# InputModule.net
KiCad netlist of a schematic drawn in EAGLE
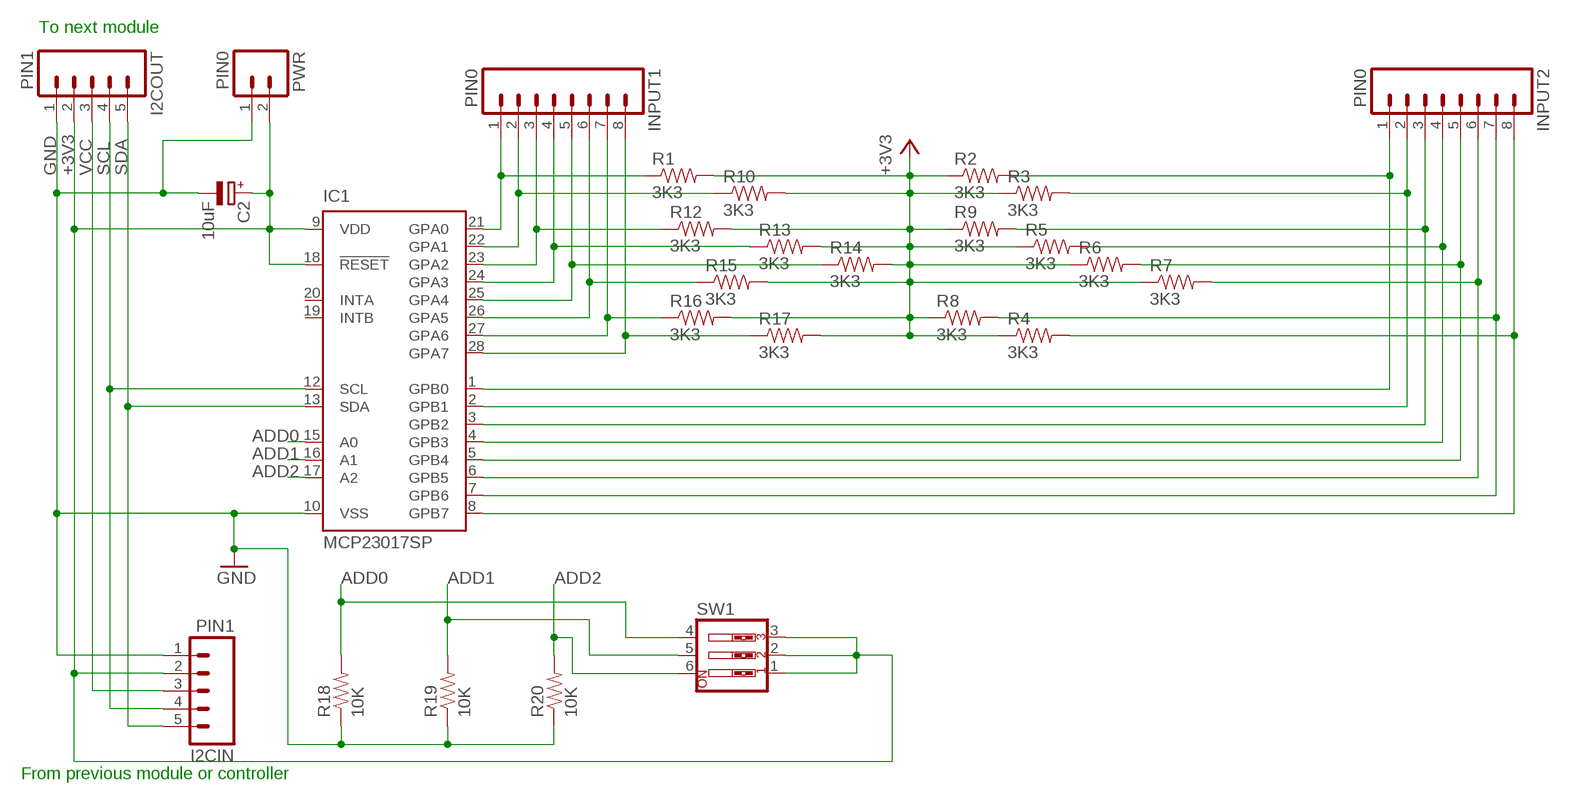
[diagram p0: schematic, sheet 1]

(export (version "E")
  (design (tool "Eeschema 10.0.6"))
  (components
    (comp (ref "C2")
      (value "10uF")
      (footprint "eagle-import:E2,5-6")
      (libsource (lib "eagle-import") (part "CPOL-EUE2.5-6"))
    )
    (comp (ref "I2CIN")
      (value "PIN1")
      (footprint "eagle-import:05P")
      (libsource (lib "eagle-import") (part "M05"))
    )
    (comp (ref "I2COUT")
      (value "PIN1")
      (footprint "eagle-import:05P")
      (libsource (lib "eagle-import") (part "M05"))
    )
    (comp (ref "IC1")
      (value "MCP23017SP")
      (footprint "eagle-import:DIL28-3")
      (fields (field (name "MF") "MICROCHIP") (field (name "MPN") "MCP23017-E/SP"))
      (libsource (lib "eagle-import") (part "MCP23017SP"))
    )
    (comp (ref "INPUT1")
      (value "PIN0")
      (footprint "eagle-import:1X08_ROUND")
      (libsource (lib "eagle-import") (part "M08"))
    )
    (comp (ref "INPUT2")
      (value "PIN0")
      (footprint "eagle-import:1X08_ROUND")
      (libsource (lib "eagle-import") (part "M08"))
    )
    (comp (ref "PWR")
      (value "PIN0")
      (footprint "eagle-import:02P")
      (libsource (lib "eagle-import") (part "M02"))
    )
    (comp (ref "R1")
      (value "3K3")
      (footprint "eagle-import:AXIAL-0.4")
      (libsource (lib "eagle-import") (part "RESISTORPTH-1/4W"))
    )
    (comp (ref "R2")
      (value "3K3")
      (footprint "eagle-import:AXIAL-0.4")
      (libsource (lib "eagle-import") (part "RESISTORPTH-1/4W"))
    )
    (comp (ref "R3")
      (value "3K3")
      (footprint "eagle-import:AXIAL-0.4")
      (libsource (lib "eagle-import") (part "RESISTORPTH-1/4W"))
    )
    (comp (ref "R4")
      (value "3K3")
      (footprint "eagle-import:AXIAL-0.4")
      (libsource (lib "eagle-import") (part "RESISTORPTH-1/4W"))
    )
    (comp (ref "R5")
      (value "3K3")
      (footprint "eagle-import:AXIAL-0.4")
      (libsource (lib "eagle-import") (part "RESISTORPTH-1/4W"))
    )
    (comp (ref "R6")
      (value "3K3")
      (footprint "eagle-import:AXIAL-0.4")
      (libsource (lib "eagle-import") (part "RESISTORPTH-1/4W"))
    )
    (comp (ref "R7")
      (value "3K3")
      (footprint "eagle-import:AXIAL-0.4")
      (libsource (lib "eagle-import") (part "RESISTORPTH-1/4W"))
    )
    (comp (ref "R8")
      (value "3K3")
      (footprint "eagle-import:AXIAL-0.4")
      (libsource (lib "eagle-import") (part "RESISTORPTH-1/4W"))
    )
    (comp (ref "R9")
      (value "3K3")
      (footprint "eagle-import:AXIAL-0.4")
      (libsource (lib "eagle-import") (part "RESISTORPTH-1/4W"))
    )
    (comp (ref "R10")
      (value "3K3")
      (footprint "eagle-import:AXIAL-0.4")
      (libsource (lib "eagle-import") (part "RESISTORPTH-1/4W"))
    )
    (comp (ref "R12")
      (value "3K3")
      (footprint "eagle-import:AXIAL-0.4")
      (libsource (lib "eagle-import") (part "RESISTORPTH-1/4W"))
    )
    (comp (ref "R13")
      (value "3K3")
      (footprint "eagle-import:AXIAL-0.4")
      (libsource (lib "eagle-import") (part "RESISTORPTH-1/4W"))
    )
    (comp (ref "R14")
      (value "3K3")
      (footprint "eagle-import:AXIAL-0.4")
      (libsource (lib "eagle-import") (part "RESISTORPTH-1/4W"))
    )
    (comp (ref "R15")
      (value "3K3")
      (footprint "eagle-import:AXIAL-0.4")
      (libsource (lib "eagle-import") (part "RESISTORPTH-1/4W"))
    )
    (comp (ref "R16")
      (value "3K3")
      (footprint "eagle-import:AXIAL-0.4")
      (libsource (lib "eagle-import") (part "RESISTORPTH-1/4W"))
    )
    (comp (ref "R17")
      (value "3K3")
      (footprint "eagle-import:AXIAL-0.4")
      (libsource (lib "eagle-import") (part "RESISTORPTH-1/4W"))
    )
    (comp (ref "R18")
      (value "10K")
      (footprint "eagle-import:AXIAL-0.4")
      (libsource (lib "eagle-import") (part "RESISTORPTH-1/4W"))
    )
    (comp (ref "R19")
      (value "10K")
      (footprint "eagle-import:AXIAL-0.4")
      (libsource (lib "eagle-import") (part "RESISTORPTH-1/4W"))
    )
    (comp (ref "R20")
      (value "10K")
      (footprint "eagle-import:AXIAL-0.4")
      (libsource (lib "eagle-import") (part "RESISTORPTH-1/4W"))
    )
    (comp (ref "SW1")
      (value "SW_DIP-3")
      (footprint "eagle-import:EDG-03")
      (libsource (lib "eagle-import") (part "SW_DIP-3"))
    )
  )
  (nets
    (net (code "1") (name "+3V3") (class "Default")
      (node (ref "C2") (pin "+") (pinfunction "+_+") (pintype "passive"))
      (node (ref "I2CIN") (pin "2") (pinfunction "2_2") (pintype "passive"))
      (node (ref "I2COUT") (pin "2") (pinfunction "2_2") (pintype "passive"))
      (node (ref "IC1") (pin "18") (pinfunction "~{RESET}_18") (pintype "input"))
      (node (ref "IC1") (pin "9") (pinfunction "VDD_9") (pintype "power_in"))
      (node (ref "PWR") (pin "2") (pinfunction "2_2") (pintype "passive"))
      (node (ref "R1") (pin "P$2") (pinfunction "2_P$2") (pintype "passive"))
      (node (ref "R10") (pin "P$2") (pinfunction "2_P$2") (pintype "passive"))
      (node (ref "R12") (pin "P$2") (pinfunction "2_P$2") (pintype "passive"))
      (node (ref "R13") (pin "P$2") (pinfunction "2_P$2") (pintype "passive"))
      (node (ref "R14") (pin "P$2") (pinfunction "2_P$2") (pintype "passive"))
      (node (ref "R15") (pin "P$2") (pinfunction "2_P$2") (pintype "passive"))
      (node (ref "R16") (pin "P$2") (pinfunction "2_P$2") (pintype "passive"))
      (node (ref "R17") (pin "P$2") (pinfunction "2_P$2") (pintype "passive"))
      (node (ref "R2") (pin "P$1") (pinfunction "1_P$1") (pintype "passive"))
      (node (ref "R3") (pin "P$1") (pinfunction "1_P$1") (pintype "passive"))
      (node (ref "R4") (pin "P$1") (pinfunction "1_P$1") (pintype "passive"))
      (node (ref "R5") (pin "P$1") (pinfunction "1_P$1") (pintype "passive"))
      (node (ref "R6") (pin "P$1") (pinfunction "1_P$1") (pintype "passive"))
      (node (ref "R7") (pin "P$1") (pinfunction "1_P$1") (pintype "passive"))
      (node (ref "R8") (pin "P$1") (pinfunction "1_P$1") (pintype "passive"))
      (node (ref "R9") (pin "P$1") (pinfunction "1_P$1") (pintype "passive"))
      (node (ref "SW1") (pin "1") (pinfunction "1_1") (pintype "passive"))
      (node (ref "SW1") (pin "2") (pinfunction "2_2") (pintype "passive"))
      (node (ref "SW1") (pin "3") (pinfunction "3_3") (pintype "passive"))
    )
    (net (code "2") (name "/ADD0") (class "Default")
      (node (ref "IC1") (pin "15") (pinfunction "A0_15") (pintype "input"))
      (node (ref "R18") (pin "P$2") (pinfunction "2_P$2") (pintype "passive"))
      (node (ref "SW1") (pin "4") (pinfunction "4_4") (pintype "passive"))
    )
    (net (code "3") (name "/ADD1") (class "Default")
      (node (ref "IC1") (pin "16") (pinfunction "A1_16") (pintype "input"))
      (node (ref "R19") (pin "P$2") (pinfunction "2_P$2") (pintype "passive"))
      (node (ref "SW1") (pin "5") (pinfunction "5_5") (pintype "passive"))
    )
    (net (code "4") (name "/ADD2") (class "Default")
      (node (ref "IC1") (pin "17") (pinfunction "A2_17") (pintype "input"))
      (node (ref "R20") (pin "P$2") (pinfunction "2_P$2") (pintype "passive"))
      (node (ref "SW1") (pin "6") (pinfunction "6_6") (pintype "passive"))
    )
    (net (code "5") (name "/SCL") (class "Default")
      (node (ref "I2CIN") (pin "4") (pinfunction "4_4") (pintype "passive"))
      (node (ref "I2COUT") (pin "4") (pinfunction "4_4") (pintype "passive"))
      (node (ref "IC1") (pin "12") (pinfunction "SCL_12") (pintype "input"))
    )
    (net (code "6") (name "/SDA") (class "Default")
      (node (ref "I2CIN") (pin "5") (pinfunction "5_5") (pintype "passive"))
      (node (ref "I2COUT") (pin "5") (pinfunction "5_5") (pintype "passive"))
      (node (ref "IC1") (pin "13") (pinfunction "SDA_13") (pintype "bidirectional"))
    )
    (net (code "7") (name "/VCC") (class "Default")
      (node (ref "I2CIN") (pin "3") (pinfunction "3_3") (pintype "passive"))
      (node (ref "I2COUT") (pin "3") (pinfunction "3_3") (pintype "passive"))
    )
    (net (code "8") (name "GND") (class "Default")
      (node (ref "C2") (pin "-") (pinfunction "-_-") (pintype "passive"))
      (node (ref "I2CIN") (pin "1") (pinfunction "1_1") (pintype "passive"))
      (node (ref "I2COUT") (pin "1") (pinfunction "1_1") (pintype "passive"))
      (node (ref "IC1") (pin "10") (pinfunction "VSS_10") (pintype "power_in"))
      (node (ref "PWR") (pin "1") (pinfunction "1_1") (pintype "passive"))
      (node (ref "R18") (pin "P$1") (pinfunction "1_P$1") (pintype "passive"))
      (node (ref "R19") (pin "P$1") (pinfunction "1_P$1") (pintype "passive"))
      (node (ref "R20") (pin "P$1") (pinfunction "1_P$1") (pintype "passive"))
    )
    (net (code "9") (name "Net-(IC1-GPA0)") (class "Default")
      (node (ref "IC1") (pin "21") (pinfunction "GPA0_21") (pintype "bidirectional"))
      (node (ref "INPUT1") (pin "1") (pinfunction "1_1") (pintype "passive"))
      (node (ref "R1") (pin "P$1") (pinfunction "1_P$1") (pintype "passive"))
    )
    (net (code "10") (name "Net-(IC1-GPA1)") (class "Default")
      (node (ref "IC1") (pin "22") (pinfunction "GPA1_22") (pintype "bidirectional"))
      (node (ref "INPUT1") (pin "2") (pinfunction "2_2") (pintype "passive"))
      (node (ref "R10") (pin "P$1") (pinfunction "1_P$1") (pintype "passive"))
    )
    (net (code "11") (name "Net-(IC1-GPA2)") (class "Default")
      (node (ref "IC1") (pin "23") (pinfunction "GPA2_23") (pintype "bidirectional"))
      (node (ref "INPUT1") (pin "3") (pinfunction "3_3") (pintype "passive"))
      (node (ref "R12") (pin "P$1") (pinfunction "1_P$1") (pintype "passive"))
    )
    (net (code "12") (name "Net-(IC1-GPA3)") (class "Default")
      (node (ref "IC1") (pin "24") (pinfunction "GPA3_24") (pintype "bidirectional"))
      (node (ref "INPUT1") (pin "4") (pinfunction "4_4") (pintype "passive"))
      (node (ref "R13") (pin "P$1") (pinfunction "1_P$1") (pintype "passive"))
    )
    (net (code "13") (name "Net-(IC1-GPA4)") (class "Default")
      (node (ref "IC1") (pin "25") (pinfunction "GPA4_25") (pintype "bidirectional"))
      (node (ref "INPUT1") (pin "5") (pinfunction "5_5") (pintype "passive"))
      (node (ref "R14") (pin "P$1") (pinfunction "1_P$1") (pintype "passive"))
    )
    (net (code "14") (name "Net-(IC1-GPA5)") (class "Default")
      (node (ref "IC1") (pin "26") (pinfunction "GPA5_26") (pintype "bidirectional"))
      (node (ref "INPUT1") (pin "6") (pinfunction "6_6") (pintype "passive"))
      (node (ref "R15") (pin "P$1") (pinfunction "1_P$1") (pintype "passive"))
    )
    (net (code "15") (name "Net-(IC1-GPA6)") (class "Default")
      (node (ref "IC1") (pin "27") (pinfunction "GPA6_27") (pintype "bidirectional"))
      (node (ref "INPUT1") (pin "7") (pinfunction "7_7") (pintype "passive"))
      (node (ref "R16") (pin "P$1") (pinfunction "1_P$1") (pintype "passive"))
    )
    (net (code "16") (name "Net-(IC1-GPA7)") (class "Default")
      (node (ref "IC1") (pin "28") (pinfunction "GPA7_28") (pintype "bidirectional"))
      (node (ref "INPUT1") (pin "8") (pinfunction "8_8") (pintype "passive"))
      (node (ref "R17") (pin "P$1") (pinfunction "1_P$1") (pintype "passive"))
    )
    (net (code "17") (name "Net-(IC1-GPB0)") (class "Default")
      (node (ref "IC1") (pin "1") (pinfunction "GPB0_1") (pintype "bidirectional"))
      (node (ref "INPUT2") (pin "1") (pinfunction "1_1") (pintype "passive"))
      (node (ref "R2") (pin "P$2") (pinfunction "2_P$2") (pintype "passive"))
    )
    (net (code "18") (name "Net-(IC1-GPB1)") (class "Default")
      (node (ref "IC1") (pin "2") (pinfunction "GPB1_2") (pintype "bidirectional"))
      (node (ref "INPUT2") (pin "2") (pinfunction "2_2") (pintype "passive"))
      (node (ref "R3") (pin "P$2") (pinfunction "2_P$2") (pintype "passive"))
    )
    (net (code "19") (name "Net-(IC1-GPB2)") (class "Default")
      (node (ref "IC1") (pin "3") (pinfunction "GPB2_3") (pintype "bidirectional"))
      (node (ref "INPUT2") (pin "3") (pinfunction "3_3") (pintype "passive"))
      (node (ref "R9") (pin "P$2") (pinfunction "2_P$2") (pintype "passive"))
    )
    (net (code "20") (name "Net-(IC1-GPB3)") (class "Default")
      (node (ref "IC1") (pin "4") (pinfunction "GPB3_4") (pintype "bidirectional"))
      (node (ref "INPUT2") (pin "4") (pinfunction "4_4") (pintype "passive"))
      (node (ref "R5") (pin "P$2") (pinfunction "2_P$2") (pintype "passive"))
    )
    (net (code "21") (name "Net-(IC1-GPB4)") (class "Default")
      (node (ref "IC1") (pin "5") (pinfunction "GPB4_5") (pintype "bidirectional"))
      (node (ref "INPUT2") (pin "5") (pinfunction "5_5") (pintype "passive"))
      (node (ref "R6") (pin "P$2") (pinfunction "2_P$2") (pintype "passive"))
    )
    (net (code "22") (name "Net-(IC1-GPB5)") (class "Default")
      (node (ref "IC1") (pin "6") (pinfunction "GPB5_6") (pintype "bidirectional"))
      (node (ref "INPUT2") (pin "6") (pinfunction "6_6") (pintype "passive"))
      (node (ref "R7") (pin "P$2") (pinfunction "2_P$2") (pintype "passive"))
    )
    (net (code "23") (name "Net-(IC1-GPB6)") (class "Default")
      (node (ref "IC1") (pin "7") (pinfunction "GPB6_7") (pintype "bidirectional"))
      (node (ref "INPUT2") (pin "7") (pinfunction "7_7") (pintype "passive"))
      (node (ref "R8") (pin "P$2") (pinfunction "2_P$2") (pintype "passive"))
    )
    (net (code "24") (name "Net-(IC1-GPB7)") (class "Default")
      (node (ref "IC1") (pin "8") (pinfunction "GPB7_8") (pintype "bidirectional"))
      (node (ref "INPUT2") (pin "8") (pinfunction "8_8") (pintype "passive"))
      (node (ref "R4") (pin "P$2") (pinfunction "2_P$2") (pintype "passive"))
    )
    (net (code "25") (name "unconnected-(IC1-INTA-Pad20)") (class "Default")
      (node (ref "IC1") (pin "20") (pinfunction "INTA_20") (pintype "output"))
    )
    (net (code "26") (name "unconnected-(IC1-INTB-Pad19)") (class "Default")
      (node (ref "IC1") (pin "19") (pinfunction "INTB_19") (pintype "output"))
    )
  )
)
